# Board_Master_PROTO_V2_Mob_Project.net
KiCad netlist of a schematic drawn in EAGLE
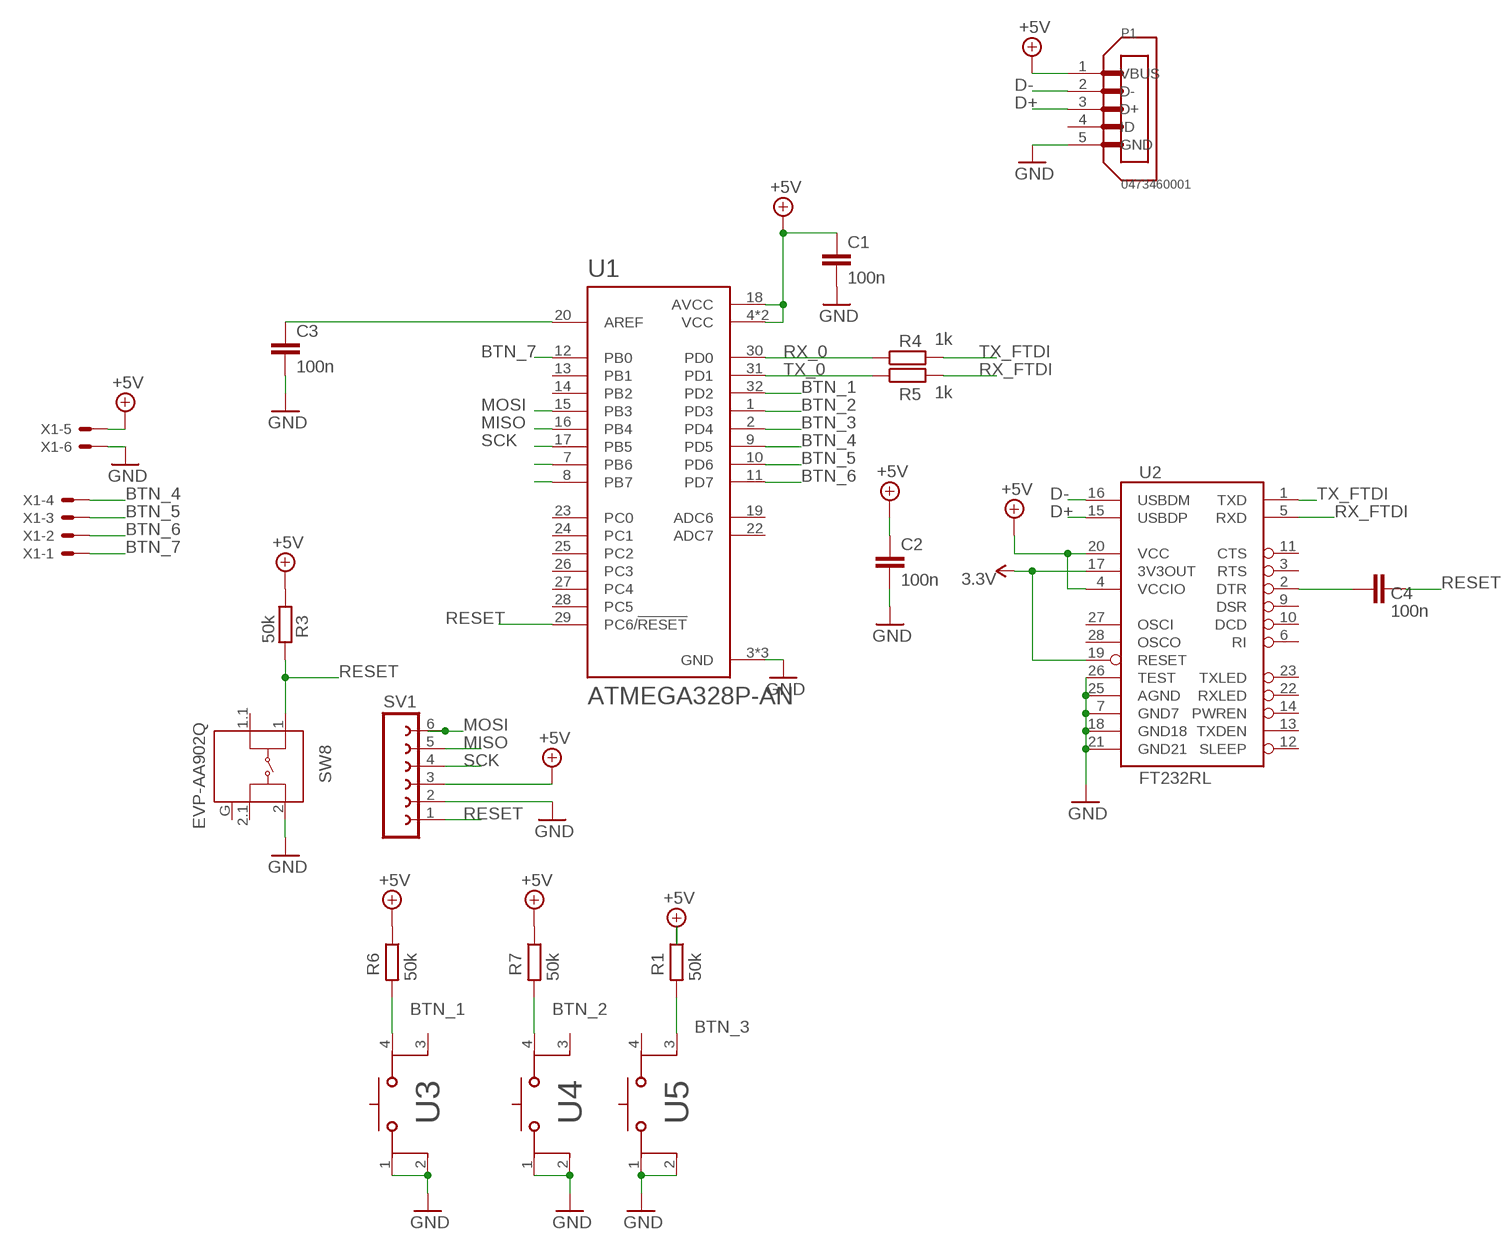
[diagram p0: schematic, sheet 1]

(export (version "E")
  (design (tool "Eeschema 10.0.6"))
  (components
    (comp (ref "C1")
      (value "100n")
      (footprint "eagle-import:CAP_0805")
      (fields
        (field (name "DIGIKEY_PART_NUMBER") "311-1140-2-ND")
        (field (name "MANUFACTURER") "Yageo")
        (field (name "MPN") "CC0805KRX7R9BB104")
        (field (name "CREATED_BY") "PCBLayout.com")
      )
      (libsource (lib "eagle-import") (part "CC0805KRX7R9BB104"))
    )
    (comp (ref "C2")
      (value "100n")
      (footprint "eagle-import:CAP_0805")
      (fields
        (field (name "DIGIKEY_PART_NUMBER") "311-1140-2-ND")
        (field (name "MANUFACTURER") "Yageo")
        (field (name "MPN") "CC0805KRX7R9BB104")
        (field (name "CREATED_BY") "PCBLayout.com")
      )
      (libsource (lib "eagle-import") (part "CC0805KRX7R9BB104"))
    )
    (comp (ref "C3")
      (value "100n")
      (footprint "eagle-import:CAP_0805")
      (fields
        (field (name "DIGIKEY_PART_NUMBER") "311-1140-2-ND")
        (field (name "MANUFACTURER") "Yageo")
        (field (name "MPN") "CC0805KRX7R9BB104")
        (field (name "CREATED_BY") "PCBLayout.com")
      )
      (libsource (lib "eagle-import") (part "CC0805KRX7R9BB104"))
    )
    (comp (ref "C4")
      (value "100n")
      (footprint "eagle-import:CAP_0805")
      (fields
        (field (name "DIGIKEY_PART_NUMBER") "311-1140-2-ND")
        (field (name "MANUFACTURER") "Yageo")
        (field (name "MPN") "CC0805KRX7R9BB104")
        (field (name "CREATED_BY") "PCBLayout.com")
      )
      (libsource (lib "eagle-import") (part "CC0805KRX7R9BB104"))
    )
    (comp (ref "P1")
      (value "0473460001")
      (footprint "eagle-import:MOLEX_0473460001")
      (fields (field (name "MF") "Weidmuller"))
      (libsource (lib "eagle-import") (part "0473460001"))
    )
    (comp (ref "R1")
      (value "50k")
      (footprint "eagle-import:R0805")
      (libsource (lib "eagle-import") (part "R-EU_R0805"))
    )
    (comp (ref "R3")
      (value "50k")
      (footprint "eagle-import:R0805")
      (libsource (lib "eagle-import") (part "R-EU_R0805"))
    )
    (comp (ref "R4")
      (value "1k")
      (footprint "eagle-import:R0805")
      (libsource (lib "eagle-import") (part "R-EU_R0805"))
    )
    (comp (ref "R5")
      (value "1k")
      (footprint "eagle-import:R0805")
      (libsource (lib "eagle-import") (part "R-EU_R0805"))
    )
    (comp (ref "R6")
      (value "50k")
      (footprint "eagle-import:R0805")
      (libsource (lib "eagle-import") (part "R-EU_R0805"))
    )
    (comp (ref "R7")
      (value "50k")
      (footprint "eagle-import:R0805")
      (libsource (lib "eagle-import") (part "R-EU_R0805"))
    )
    (comp (ref "SV1")
      (value "FE06-1")
      (footprint "eagle-import:FE06")
      (libsource (lib "eagle-import") (part "FE06-1"))
    )
    (comp (ref "SW8")
      (value "EVP-AA902Q")
      (footprint "eagle-import:EVP-AA902Q")
      (fields
        (field (name "DIGIKEY_PARTNO") "P15193TR-ND")
        (field (name "MANUFACTURER") "Panasonic Electronic Components")
        (field (name "CREATED_BY") "PCBLayout.com")
      )
      (libsource (lib "eagle-import") (part "EVP-AA902Q"))
    )
    (comp (ref "U1")
      (value "ATMEGA328P-AN")
      (footprint "eagle-import:QFP80P900X900X120-32N")
      (fields (field (name "MF") "Microchip"))
      (libsource (lib "eagle-import") (part "ATMEGA328P-AN"))
    )
    (comp (ref "U2")
      (value "FT232RL")
      (footprint "eagle-import:SSOP28DB")
      (libsource (lib "eagle-import") (part "FT232RLSSOP"))
    )
    (comp (ref "U3")
      (value "4-1437565-1")
      (footprint "eagle-import:SW4_236X236H5MM")
      (fields (field (name "COPYRIGHT") "Copyright (C) 2016 Accelerated Designs. All rights reserved"))
      (libsource (lib "eagle-import") (part "4-1437565-1"))
    )
    (comp (ref "U4")
      (value "4-1437565-1")
      (footprint "eagle-import:SW4_236X236H5MM")
      (fields (field (name "COPYRIGHT") "Copyright (C) 2016 Accelerated Designs. All rights reserved"))
      (libsource (lib "eagle-import") (part "4-1437565-1"))
    )
    (comp (ref "U5")
      (value "4-1437565-1")
      (footprint "eagle-import:SW4_236X236H5MM")
      (fields (field (name "COPYRIGHT") "Copyright (C) 2016 Accelerated Designs. All rights reserved"))
      (libsource (lib "eagle-import") (part "4-1437565-1"))
    )
    (comp (ref "X1")
      (value "C-GRID-06-70543")
      (footprint "eagle-import:70543-06")
      (fields (field (name "MF") "MOLEX"))
      (libsource (lib "eagle-import") (part "C-GRID-06-70543"))
    )
  )
  (nets
    (net (code "1") (name "+5V") (class "Default")
      (node (ref "C1") (pin "1") (pinfunction "1_1") (pintype "passive"))
      (node (ref "C2") (pin "1") (pinfunction "1_1") (pintype "passive"))
      (node (ref "P1") (pin "1") (pinfunction "VBUS_1") (pintype "power_in"))
      (node (ref "R1") (pin "1") (pinfunction "1_1") (pintype "passive"))
      (node (ref "R3") (pin "1") (pinfunction "1_1") (pintype "passive"))
      (node (ref "R6") (pin "1") (pinfunction "1_1") (pintype "passive"))
      (node (ref "R7") (pin "1") (pinfunction "1_1") (pintype "passive"))
      (node (ref "SV1") (pin "3") (pinfunction "3_3") (pintype "passive"))
      (node (ref "U1") (pin "18") (pinfunction "AVCC_18") (pintype "power_in"))
      (node (ref "U1") (pin "4") (pinfunction "VCC_4") (pintype "power_in"))
      (node (ref "U1") (pin "6") (pinfunction "VCC_6") (pintype "power_in"))
      (node (ref "U2") (pin "20") (pinfunction "VCC_20") (pintype "power_in"))
      (node (ref "U2") (pin "4") (pinfunction "VCCIO_4") (pintype "power_in"))
      (node (ref "X1") (pin "5") (pinfunction "S_5") (pintype "passive"))
    )
    (net (code "2") (name "/BTN_1") (class "Default")
      (node (ref "R6") (pin "2") (pinfunction "2_2") (pintype "passive"))
      (node (ref "U1") (pin "32") (pinfunction "PD2_32") (pintype "bidirectional"))
      (node (ref "U3") (pin "4") (pinfunction "4_4") (pintype "passive"))
    )
    (net (code "3") (name "/BTN_2") (class "Default")
      (node (ref "R7") (pin "2") (pinfunction "2_2") (pintype "passive"))
      (node (ref "U1") (pin "1") (pinfunction "PD3_1") (pintype "bidirectional"))
      (node (ref "U4") (pin "4") (pinfunction "4_4") (pintype "passive"))
    )
    (net (code "4") (name "/BTN_3") (class "Default")
      (node (ref "R1") (pin "2") (pinfunction "2_2") (pintype "passive"))
      (node (ref "U1") (pin "2") (pinfunction "PD4_2") (pintype "bidirectional"))
      (node (ref "U5") (pin "3") (pinfunction "3_3") (pintype "passive"))
    )
    (net (code "5") (name "/BTN_4") (class "Default")
      (node (ref "U1") (pin "9") (pinfunction "PD5_9") (pintype "bidirectional"))
      (node (ref "X1") (pin "4") (pinfunction "S_4") (pintype "passive"))
    )
    (net (code "6") (name "/BTN_5") (class "Default")
      (node (ref "U1") (pin "10") (pinfunction "PD6_10") (pintype "bidirectional"))
      (node (ref "X1") (pin "3") (pinfunction "S_3") (pintype "passive"))
    )
    (net (code "7") (name "/BTN_6") (class "Default")
      (node (ref "U1") (pin "11") (pinfunction "PD7_11") (pintype "bidirectional"))
      (node (ref "X1") (pin "2") (pinfunction "S_2") (pintype "passive"))
    )
    (net (code "8") (name "/BTN_7") (class "Default")
      (node (ref "U1") (pin "12") (pinfunction "PB0_12") (pintype "bidirectional"))
      (node (ref "X1") (pin "1") (pinfunction "S_1") (pintype "passive"))
    )
    (net (code "9") (name "/D+") (class "Default")
      (node (ref "P1") (pin "3") (pinfunction "D+_3") (pintype "bidirectional"))
      (node (ref "U2") (pin "15") (pinfunction "USBDP_15") (pintype "bidirectional"))
    )
    (net (code "10") (name "/D-") (class "Default")
      (node (ref "P1") (pin "2") (pinfunction "D-_2") (pintype "bidirectional"))
      (node (ref "U2") (pin "16") (pinfunction "USBDM_16") (pintype "bidirectional"))
    )
    (net (code "11") (name "/MISO") (class "Default")
      (node (ref "SV1") (pin "5") (pinfunction "5_5") (pintype "passive"))
      (node (ref "U1") (pin "16") (pinfunction "PB4_16") (pintype "bidirectional"))
    )
    (net (code "12") (name "/MOSI") (class "Default")
      (node (ref "SV1") (pin "6") (pinfunction "6_6") (pintype "passive"))
      (node (ref "U1") (pin "15") (pinfunction "PB3_15") (pintype "bidirectional"))
    )
    (net (code "13") (name "/RESET") (class "Default")
      (node (ref "C4") (pin "1") (pinfunction "1_1") (pintype "passive"))
      (node (ref "R3") (pin "2") (pinfunction "2_2") (pintype "passive"))
      (node (ref "SV1") (pin "1") (pinfunction "1_1") (pintype "passive"))
      (node (ref "SW8") (pin "1") (pinfunction "1_1") (pintype "passive"))
      (node (ref "U1") (pin "29") (pinfunction "PC6/~{RESET}_29") (pintype "bidirectional"))
    )
    (net (code "14") (name "/RX_0") (class "Default")
      (node (ref "R4") (pin "1") (pinfunction "1_1") (pintype "passive"))
      (node (ref "U1") (pin "30") (pinfunction "PD0_30") (pintype "bidirectional"))
    )
    (net (code "15") (name "/RX_FTDI") (class "Default")
      (node (ref "R5") (pin "2") (pinfunction "2_2") (pintype "passive"))
      (node (ref "U2") (pin "5") (pinfunction "RXD_5") (pintype "input"))
    )
    (net (code "16") (name "/SCK") (class "Default")
      (node (ref "SV1") (pin "4") (pinfunction "4_4") (pintype "passive"))
      (node (ref "U1") (pin "17") (pinfunction "PB5_17") (pintype "bidirectional"))
    )
    (net (code "17") (name "/TX_0") (class "Default")
      (node (ref "R5") (pin "1") (pinfunction "1_1") (pintype "passive"))
      (node (ref "U1") (pin "31") (pinfunction "PD1_31") (pintype "bidirectional"))
    )
    (net (code "18") (name "/TX_FTDI") (class "Default")
      (node (ref "R4") (pin "2") (pinfunction "2_2") (pintype "passive"))
      (node (ref "U2") (pin "1") (pinfunction "TXD_1") (pintype "output"))
    )
    (net (code "19") (name "3.3V") (class "Default")
      (node (ref "U2") (pin "17") (pinfunction "3V3OUT_17") (pintype "output"))
      (node (ref "U2") (pin "19") (pinfunction "RESET_19") (pintype "input"))
    )
    (net (code "20") (name "GND") (class "Default")
      (node (ref "C1") (pin "2") (pinfunction "2_2") (pintype "passive"))
      (node (ref "C2") (pin "2") (pinfunction "2_2") (pintype "passive"))
      (node (ref "C3") (pin "2") (pinfunction "2_2") (pintype "passive"))
      (node (ref "P1") (pin "5") (pinfunction "GND_5") (pintype "passive"))
      (node (ref "SV1") (pin "2") (pinfunction "2_2") (pintype "passive"))
      (node (ref "SW8") (pin "2") (pinfunction "2_2") (pintype "passive"))
      (node (ref "U1") (pin "21") (pinfunction "GND_21") (pintype "power_in"))
      (node (ref "U1") (pin "3") (pinfunction "GND_3") (pintype "power_in"))
      (node (ref "U1") (pin "5") (pinfunction "GND_5") (pintype "power_in"))
      (node (ref "U2") (pin "18") (pinfunction "GND18_18") (pintype "power_in"))
      (node (ref "U2") (pin "21") (pinfunction "GND21_21") (pintype "power_in"))
      (node (ref "U2") (pin "25") (pinfunction "AGND_25") (pintype "power_in"))
      (node (ref "U2") (pin "26") (pinfunction "TEST_26") (pintype "input"))
      (node (ref "U2") (pin "7") (pinfunction "GND7_7") (pintype "power_in"))
      (node (ref "U3") (pin "1") (pinfunction "1_1") (pintype "passive"))
      (node (ref "U3") (pin "2") (pinfunction "2_2") (pintype "passive"))
      (node (ref "U4") (pin "1") (pinfunction "1_1") (pintype "passive"))
      (node (ref "U4") (pin "2") (pinfunction "2_2") (pintype "passive"))
      (node (ref "U5") (pin "1") (pinfunction "1_1") (pintype "passive"))
      (node (ref "U5") (pin "2") (pinfunction "2_2") (pintype "passive"))
      (node (ref "X1") (pin "6") (pinfunction "S_6") (pintype "passive"))
    )
    (net (code "21") (name "Net-(U1-AREF)") (class "Default")
      (node (ref "C3") (pin "1") (pinfunction "1_1") (pintype "passive"))
      (node (ref "U1") (pin "20") (pinfunction "AREF_20") (pintype "input"))
    )
    (net (code "22") (name "Net-(U2-DTR)") (class "Default")
      (node (ref "C4") (pin "2") (pinfunction "2_2") (pintype "passive"))
      (node (ref "U2") (pin "2") (pinfunction "DTR_2") (pintype "output"))
    )
    (net (code "23") (name "unconnected-(P1-ID-Pad4)") (class "Default")
      (node (ref "P1") (pin "4") (pinfunction "ID_4") (pintype "bidirectional"))
    )
    (net (code "24") (name "unconnected-(SW8-Pad1.1)") (class "Default")
      (node (ref "SW8") (pin "1.1") (pinfunction "1.1_1.1") (pintype "passive"))
    )
    (net (code "25") (name "unconnected-(SW8-Pad2.1)") (class "Default")
      (node (ref "SW8") (pin "2.1") (pinfunction "2.1_2.1") (pintype "passive"))
    )
    (net (code "26") (name "unconnected-(SW8-SHIELD-PadG)") (class "Default")
      (node (ref "SW8") (pin "G") (pinfunction "SHIELD_G") (pintype "passive"))
    )
    (net (code "27") (name "unconnected-(U1-ADC6-Pad19)") (class "Default")
      (node (ref "U1") (pin "19") (pinfunction "ADC6_19") (pintype "bidirectional"))
    )
    (net (code "28") (name "unconnected-(U1-ADC7-Pad22)") (class "Default")
      (node (ref "U1") (pin "22") (pinfunction "ADC7_22") (pintype "bidirectional"))
    )
    (net (code "29") (name "unconnected-(U1-PB1-Pad13)") (class "Default")
      (node (ref "U1") (pin "13") (pinfunction "PB1_13") (pintype "bidirectional"))
    )
    (net (code "30") (name "unconnected-(U1-PB2-Pad14)") (class "Default")
      (node (ref "U1") (pin "14") (pinfunction "PB2_14") (pintype "bidirectional"))
    )
    (net (code "31") (name "unconnected-(U1-PB6-Pad7)") (class "Default")
      (node (ref "U1") (pin "7") (pinfunction "PB6_7") (pintype "bidirectional"))
    )
    (net (code "32") (name "unconnected-(U1-PB7-Pad8)") (class "Default")
      (node (ref "U1") (pin "8") (pinfunction "PB7_8") (pintype "bidirectional"))
    )
    (net (code "33") (name "unconnected-(U1-PC0-Pad23)") (class "Default")
      (node (ref "U1") (pin "23") (pinfunction "PC0_23") (pintype "bidirectional"))
    )
    (net (code "34") (name "unconnected-(U1-PC1-Pad24)") (class "Default")
      (node (ref "U1") (pin "24") (pinfunction "PC1_24") (pintype "bidirectional"))
    )
    (net (code "35") (name "unconnected-(U1-PC2-Pad25)") (class "Default")
      (node (ref "U1") (pin "25") (pinfunction "PC2_25") (pintype "bidirectional"))
    )
    (net (code "36") (name "unconnected-(U1-PC3-Pad26)") (class "Default")
      (node (ref "U1") (pin "26") (pinfunction "PC3_26") (pintype "bidirectional"))
    )
    (net (code "37") (name "unconnected-(U1-PC4-Pad27)") (class "Default")
      (node (ref "U1") (pin "27") (pinfunction "PC4_27") (pintype "bidirectional"))
    )
    (net (code "38") (name "unconnected-(U1-PC5-Pad28)") (class "Default")
      (node (ref "U1") (pin "28") (pinfunction "PC5_28") (pintype "bidirectional"))
    )
    (net (code "39") (name "unconnected-(U2-CTS-Pad11)") (class "Default")
      (node (ref "U2") (pin "11") (pinfunction "CTS_11") (pintype "input"))
    )
    (net (code "40") (name "unconnected-(U2-DCD-Pad10)") (class "Default")
      (node (ref "U2") (pin "10") (pinfunction "DCD_10") (pintype "input"))
    )
    (net (code "41") (name "unconnected-(U2-DSR-Pad9)") (class "Default")
      (node (ref "U2") (pin "9") (pinfunction "DSR_9") (pintype "input"))
    )
    (net (code "42") (name "unconnected-(U2-OSCI-Pad27)") (class "Default")
      (node (ref "U2") (pin "27") (pinfunction "OSCI_27") (pintype "input"))
    )
    (net (code "43") (name "unconnected-(U2-OSCO-Pad28)") (class "Default")
      (node (ref "U2") (pin "28") (pinfunction "OSCO_28") (pintype "output"))
    )
    (net (code "44") (name "unconnected-(U2-PWREN-Pad14)") (class "Default")
      (node (ref "U2") (pin "14") (pinfunction "PWREN_14") (pintype "input"))
    )
    (net (code "45") (name "unconnected-(U2-RI-Pad6)") (class "Default")
      (node (ref "U2") (pin "6") (pinfunction "RI_6") (pintype "input"))
    )
    (net (code "46") (name "unconnected-(U2-RTS-Pad3)") (class "Default")
      (node (ref "U2") (pin "3") (pinfunction "RTS_3") (pintype "output"))
    )
    (net (code "47") (name "unconnected-(U2-RXLED-Pad22)") (class "Default")
      (node (ref "U2") (pin "22") (pinfunction "RXLED_22") (pintype "input"))
    )
    (net (code "48") (name "unconnected-(U2-SLEEP-Pad12)") (class "Default")
      (node (ref "U2") (pin "12") (pinfunction "SLEEP_12") (pintype "input"))
    )
    (net (code "49") (name "unconnected-(U2-TXDEN-Pad13)") (class "Default")
      (node (ref "U2") (pin "13") (pinfunction "TXDEN_13") (pintype "input"))
    )
    (net (code "50") (name "unconnected-(U2-TXLED-Pad23)") (class "Default")
      (node (ref "U2") (pin "23") (pinfunction "TXLED_23") (pintype "input"))
    )
    (net (code "51") (name "unconnected-(U3-Pad3)") (class "Default")
      (node (ref "U3") (pin "3") (pinfunction "3_3") (pintype "passive"))
    )
    (net (code "52") (name "unconnected-(U4-Pad3)") (class "Default")
      (node (ref "U4") (pin "3") (pinfunction "3_3") (pintype "passive"))
    )
    (net (code "53") (name "unconnected-(U5-Pad4)") (class "Default")
      (node (ref "U5") (pin "4") (pinfunction "4_4") (pintype "passive"))
    )
  )
)
